# Indicator_SH.net
KiCad netlist of a schematic drawn in Altium Designer
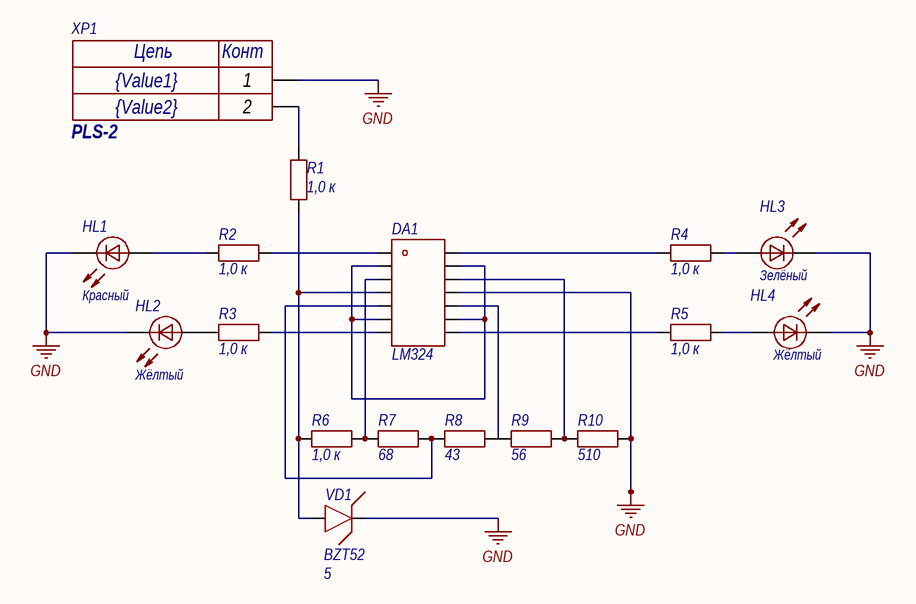
[diagram p0: Indicator_SH.SchDoc]

(export (version "E")
  (design (tool "Eeschema 10.0.6"))
  (components
    (comp (ref "DA1") (value "LM324") (footprint "SOIC-14:SOIC-14") (libsource (lib "LM324") (part "LM324")))
    (comp (ref "HL1")
      (value "Красный")
      (footprint "0603D_red")
      (description "Светодиод 0603 Красный")
      (fields (field (name "PART NUMBER") "LED 0603 RED") (field (name "АВТОР") "rreali"))
      (libsource (lib "Hydrolib") (part "LED"))
    )
    (comp (ref "HL2")
      (value "Жёлтый")
      (footprint "0603D_yellow")
      (description "Светодиод 0603 Жёлтый")
      (fields (field (name "PART NUMBER") "LED 0603 YELLOW") (field (name "АВТОР") "rreali"))
      (libsource (lib "Hydrolib") (part "LED"))
    )
    (comp (ref "HL3")
      (value "Зелёный")
      (footprint "0603D_green")
      (description "Светодиод 0603 Зелёный")
      (fields (field (name "PART NUMBER") "LED 0603 GREEN") (field (name "АВТОР") "rreali"))
      (libsource (lib "Hydrolib") (part "LED"))
    )
    (comp (ref "HL4")
      (value "Жёлтый")
      (footprint "0603D_yellow")
      (description "Светодиод 0603 Жёлтый")
      (fields (field (name "PART NUMBER") "LED 0603 YELLOW") (field (name "АВТОР") "rreali"))
      (libsource (lib "Hydrolib") (part "LED"))
    )
    (comp (ref "R1")
      (value "1,0 к")
      (footprint "0603R")
      (description "Резистор номиналом 1,0 кОм 1%")
      (fields (field (name "PART NUMBER") "Resistor_1.0k_1_0603") (field (name "TOLERANCE") "1%"))
      (libsource (lib "") (part "Resistor_1"))
    )
    (comp (ref "R2")
      (value "1,0 к")
      (footprint "0603R")
      (description "Резистор номиналом 1,0 кОм 1%")
      (fields (field (name "PART NUMBER") "Resistor_1.0k_1_0603") (field (name "TOLERANCE") "1%"))
      (libsource (lib "Hydrolib") (part "Resistor"))
    )
    (comp (ref "R3")
      (value "1,0 к")
      (footprint "0603R")
      (description "Резистор номиналом 1,0 кОм 1%")
      (fields (field (name "PART NUMBER") "Resistor_1.0k_1_0603") (field (name "TOLERANCE") "1%"))
      (libsource (lib "Hydrolib") (part "Resistor"))
    )
    (comp (ref "R4")
      (value "1,0 к")
      (footprint "0603R")
      (description "Резистор номиналом 1,0 кОм 1%")
      (fields (field (name "PART NUMBER") "Resistor_1.0k_1_0603") (field (name "TOLERANCE") "1%"))
      (libsource (lib "Hydrolib") (part "Resistor"))
    )
    (comp (ref "R5")
      (value "1,0 к")
      (footprint "0603R")
      (description "Резистор номиналом 1,0 кОм 1%")
      (fields (field (name "PART NUMBER") "Resistor_1.0k_1_0603") (field (name "TOLERANCE") "1%"))
      (libsource (lib "Hydrolib") (part "Resistor"))
    )
    (comp (ref "R6")
      (value "1,0 к")
      (footprint "0603R")
      (description "Резистор номиналом 1,0 кОм 1%")
      (fields (field (name "PART NUMBER") "Resistor_1.0k_1_0603") (field (name "TOLERANCE") "1%"))
      (libsource (lib "Hydrolib") (part "Resistor"))
    )
    (comp (ref "R7")
      (value "68")
      (footprint "0603R")
      (description "Резистор номиналом 68 Ом 1%")
      (fields (field (name "PART NUMBER") "Resistor_68_1_0603") (field (name "TOLERANCE") "1%"))
      (libsource (lib "Hydrolib") (part "Resistor"))
    )
    (comp (ref "R8")
      (value "43")
      (footprint "0603R")
      (description "Резистор номиналом 43 Ом 1%")
      (fields (field (name "PART NUMBER") "Resistor_43_1_0603") (field (name "TOLERANCE") "1%"))
      (libsource (lib "Hydrolib") (part "Resistor"))
    )
    (comp (ref "R9")
      (value "56")
      (footprint "0603R")
      (description "Резистор номиналом 56 Ом 1%")
      (fields (field (name "PART NUMBER") "Resistor_56_1_0603") (field (name "TOLERANCE") "1%"))
      (libsource (lib "Hydrolib") (part "Resistor"))
    )
    (comp (ref "R10")
      (value "510")
      (footprint "0603R")
      (description "Резистор номиналом 510 Ом 1%")
      (fields (field (name "PART NUMBER") "Resistor_510_1_0603") (field (name "TOLERANCE") "1%"))
      (libsource (lib "Hydrolib") (part "Resistor"))
    )
    (comp (ref "VD1")
      (value "BZT52")
      (footprint "SOD-323:SOD-323")
      (fields (field (name "НАПРЯЖЕНИЕ") "5"))
      (libsource (lib "BZT52") (part "BZT52"))
    )
    (comp (ref "XP1")
      (value "PLS-2")
      (footprint "PLS2")
      (description "Гребенка 2 пина")
      (fields
        (field (name "VALUE2") "{Value2}")
        (field (name "VALUE1") "{Value1}")
        (field (name "АВТОР") "rreali")
      )
      (libsource (lib "Hydrolib") (part "Conn_2pin"))
    )
  )
  (nets
    (net (code "1") (name "GND") (class "Default")
      (node (ref "DA1") (pin "11") (pinfunction "GND_11") (pintype "passive"))
      (node (ref "HL1") (pin "2") (pinfunction "2_2") (pintype "passive"))
      (node (ref "HL2") (pin "2") (pinfunction "2_2") (pintype "passive"))
      (node (ref "HL3") (pin "2") (pinfunction "2_2") (pintype "passive"))
      (node (ref "HL4") (pin "2") (pinfunction "2_2") (pintype "passive"))
      (node (ref "R10") (pin "2") (pinfunction "2_2") (pintype "passive"))
      (node (ref "VD1") (pin "2") (pinfunction "2_2") (pintype "passive"))
      (node (ref "XP1") (pin "1") (pinfunction "1_1") (pintype "passive"))
    )
    (net (code "2") (name "Net-(DA1-IN1+)") (class "Default")
      (node (ref "DA1") (pin "3") (pinfunction "IN1+_3") (pintype "passive"))
      (node (ref "R6") (pin "2") (pinfunction "2_2") (pintype "passive"))
      (node (ref "R7") (pin "1") (pinfunction "1_1") (pintype "passive"))
    )
    (net (code "3") (name "Net-(DA1-IN1-)") (class "Default")
      (node (ref "DA1") (pin "13") (pinfunction "IN4-_13") (pintype "passive"))
      (node (ref "DA1") (pin "2") (pinfunction "IN1-_2") (pintype "passive"))
      (node (ref "DA1") (pin "6") (pinfunction "IN2-_6") (pintype "passive"))
      (node (ref "DA1") (pin "9") (pinfunction "IN3-_9") (pintype "passive"))
    )
    (net (code "4") (name "Net-(DA1-IN2+)") (class "Default")
      (node (ref "DA1") (pin "5") (pinfunction "IN2+_5") (pintype "passive"))
      (node (ref "R7") (pin "2") (pinfunction "2_2") (pintype "passive"))
      (node (ref "R8") (pin "1") (pinfunction "1_1") (pintype "passive"))
    )
    (net (code "5") (name "Net-(DA1-IN3+)") (class "Default")
      (node (ref "DA1") (pin "10") (pinfunction "IN3+_10") (pintype "passive"))
      (node (ref "R8") (pin "2") (pinfunction "2_2") (pintype "passive"))
      (node (ref "R9") (pin "1") (pinfunction "1_1") (pintype "passive"))
    )
    (net (code "6") (name "Net-(DA1-IN4+)") (class "Default")
      (node (ref "DA1") (pin "12") (pinfunction "IN4+_12") (pintype "passive"))
      (node (ref "R10") (pin "1") (pinfunction "1_1") (pintype "passive"))
      (node (ref "R9") (pin "2") (pinfunction "2_2") (pintype "passive"))
    )
    (net (code "7") (name "Net-(DA1-OUT1)") (class "Default")
      (node (ref "DA1") (pin "1") (pinfunction "OUT1_1") (pintype "passive"))
      (node (ref "R2") (pin "2") (pinfunction "2_2") (pintype "passive"))
    )
    (net (code "8") (name "Net-(DA1-OUT2)") (class "Default")
      (node (ref "DA1") (pin "7") (pinfunction "OUT2_7") (pintype "passive"))
      (node (ref "R3") (pin "2") (pinfunction "2_2") (pintype "passive"))
    )
    (net (code "9") (name "Net-(DA1-OUT3)") (class "Default")
      (node (ref "DA1") (pin "8") (pinfunction "OUT3_8") (pintype "passive"))
      (node (ref "R5") (pin "1") (pinfunction "1_1") (pintype "passive"))
    )
    (net (code "10") (name "Net-(DA1-OUT4)") (class "Default")
      (node (ref "DA1") (pin "14") (pinfunction "OUT4_14") (pintype "passive"))
      (node (ref "R4") (pin "1") (pinfunction "1_1") (pintype "passive"))
    )
    (net (code "11") (name "Net-(DA1-VCC)") (class "Default")
      (node (ref "DA1") (pin "4") (pinfunction "VCC_4") (pintype "passive"))
      (node (ref "R1") (pin "1") (pinfunction "1_1") (pintype "passive"))
      (node (ref "R6") (pin "1") (pinfunction "1_1") (pintype "passive"))
      (node (ref "VD1") (pin "1") (pinfunction "1_1") (pintype "passive"))
    )
    (net (code "12") (name "Net-(HL1-Pad1)") (class "Default")
      (node (ref "HL1") (pin "1") (pinfunction "1_1") (pintype "passive"))
      (node (ref "R2") (pin "1") (pinfunction "1_1") (pintype "passive"))
    )
    (net (code "13") (name "Net-(HL2-Pad1)") (class "Default")
      (node (ref "HL2") (pin "1") (pinfunction "1_1") (pintype "passive"))
      (node (ref "R3") (pin "1") (pinfunction "1_1") (pintype "passive"))
    )
    (net (code "14") (name "Net-(HL3-Pad1)") (class "Default")
      (node (ref "HL3") (pin "1") (pinfunction "1_1") (pintype "passive"))
      (node (ref "R4") (pin "2") (pinfunction "2_2") (pintype "passive"))
    )
    (net (code "15") (name "Net-(HL4-Pad1)") (class "Default")
      (node (ref "HL4") (pin "1") (pinfunction "1_1") (pintype "passive"))
      (node (ref "R5") (pin "2") (pinfunction "2_2") (pintype "passive"))
    )
    (net (code "16") (name "Net-(R1-Pad2)") (class "Default")
      (node (ref "R1") (pin "2") (pinfunction "2_2") (pintype "passive"))
      (node (ref "XP1") (pin "2") (pinfunction "2_2") (pintype "passive"))
    )
  )
)
